# STM32_LED_FROM_MUSIC.net
KiCad netlist of a schematic drawn in Altium Designer
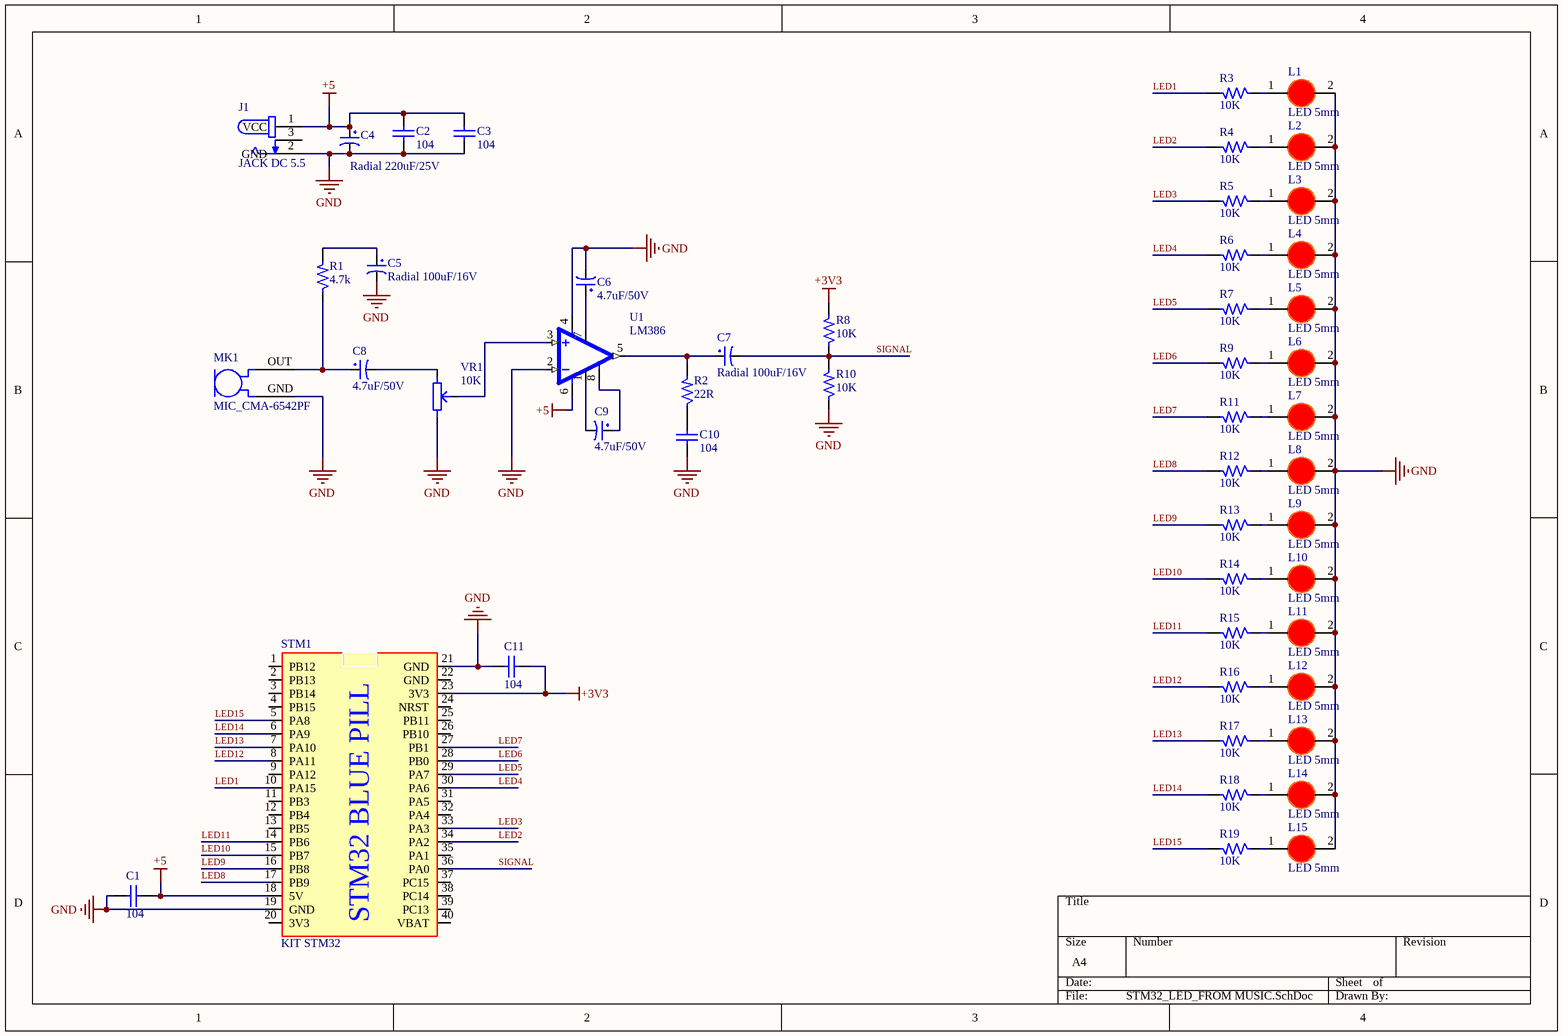
[diagram p0: STM32_LED_FROM MUSIC.SchDoc]

(export (version "E")
  (design (tool "Eeschema 10.0.6"))
  (components
    (comp (ref "C1")
      (value "104")
      (footprint "Cap Ceramic 0805")
      (description "Cap Ceramic SMD")
      (libsource (lib "KS Chuong Real") (part "CAP Ceramic SMD"))
    )
    (comp (ref "C2")
      (value "104")
      (footprint "Cap Ceramic 0805")
      (description "Cap Ceramic SMD")
      (libsource (lib "KS Chuong Real") (part "CAP Ceramic SMD"))
    )
    (comp (ref "C3")
      (value "104")
      (footprint "Cap Ceramic 0805")
      (description "Cap Ceramic SMD")
      (libsource (lib "KS Chuong Real") (part "CAP Ceramic SMD"))
    )
    (comp (ref "C4")
      (value "Radial 220uF/25V")
      (footprint "Radial 6.3x12mm")
      (libsource (lib "KS Chuong Real") (part "Radial 220uF/25V"))
    )
    (comp (ref "C5")
      (value "Radial 100uF/16V")
      (footprint "Radial 5x11mm")
      (libsource (lib "KS Chuong Real") (part "Radial 100uF/16V"))
    )
    (comp (ref "C6")
      (value "4.7uF/50V")
      (footprint "Radial 4.7uF/50V")
      (description "Radial 4.7uF/50V")
      (libsource (lib "") (part "Radial 4.7uF/50V_2"))
    )
    (comp (ref "C7")
      (value "Radial 100uF/16V")
      (footprint "Radial 5x11mm")
      (libsource (lib "") (part "Radial 100uF/16V_1"))
    )
    (comp (ref "C8")
      (value "4.7uF/50V")
      (footprint "Radial 4.7uF/50V")
      (description "Radial 4.7uF/50V")
      (libsource (lib "") (part "Radial 4.7uF/50V_1"))
    )
    (comp (ref "C9")
      (value "4.7uF/50V")
      (footprint "Radial 4.7uF/50V")
      (description "Radial 4.7uF/50V")
      (libsource (lib "KS Chuong Real") (part "Radial 4.7uF/50V"))
    )
    (comp (ref "C10")
      (value "104")
      (footprint "Cap Ceramic 0805")
      (description "Cap Ceramic SMD")
      (libsource (lib "KS Chuong Real") (part "CAP Ceramic SMD"))
    )
    (comp (ref "C11")
      (value "104")
      (footprint "Cap Ceramic 0805")
      (description "Cap Ceramic SMD")
      (libsource (lib "KS Chuong Real") (part "CAP Ceramic SMD"))
    )
    (comp (ref "J1")
      (value "JACK DC 5.5")
      (footprint "JACK DC")
      (description "2,0 x 6,5 mm, 2,5 A, Yatay, A莽谋k Delik, Dc G眉莽 Jak谋 Konnekt枚r眉")
      (fields (field (name "MF") "CUI Devices") (field (name "MP") "PJ-002A"))
      (libsource (lib "KS Chuong Real") (part "JACK DC 5.5"))
    )
    (comp (ref "L1")
      (value "LED 5mm")
      (footprint "LED-5MM-RED")
      (description "Cắm")
      (libsource (lib "KS Chuong Real") (part "LED 5mm Red"))
    )
    (comp (ref "L2")
      (value "LED 5mm")
      (footprint "LED-5MM-RED")
      (description "Cắm")
      (libsource (lib "KS Chuong Real") (part "LED 5mm Red"))
    )
    (comp (ref "L3")
      (value "LED 5mm")
      (footprint "LED-5MM-RED")
      (description "Cắm")
      (libsource (lib "KS Chuong Real") (part "LED 5mm Red"))
    )
    (comp (ref "L4")
      (value "LED 5mm")
      (footprint "LED-5MM-RED")
      (description "Cắm")
      (libsource (lib "KS Chuong Real") (part "LED 5mm Red"))
    )
    (comp (ref "L5")
      (value "LED 5mm")
      (footprint "LED-5MM-RED")
      (description "Cắm")
      (libsource (lib "KS Chuong Real") (part "LED 5mm Red"))
    )
    (comp (ref "L6")
      (value "LED 5mm")
      (footprint "LED-5MM-RED")
      (description "Cắm")
      (libsource (lib "KS Chuong Real") (part "LED 5mm Red"))
    )
    (comp (ref "L7")
      (value "LED 5mm")
      (footprint "LED-5MM-RED")
      (description "Cắm")
      (libsource (lib "KS Chuong Real") (part "LED 5mm Red"))
    )
    (comp (ref "L8")
      (value "LED 5mm")
      (footprint "LED-5MM-RED")
      (description "Cắm")
      (libsource (lib "KS Chuong Real") (part "LED 5mm Red"))
    )
    (comp (ref "L9")
      (value "LED 5mm")
      (footprint "LED-5MM-RED")
      (description "Cắm")
      (libsource (lib "KS Chuong Real") (part "LED 5mm Red"))
    )
    (comp (ref "L10")
      (value "LED 5mm")
      (footprint "LED-5MM-RED")
      (description "Cắm")
      (libsource (lib "KS Chuong Real") (part "LED 5mm Red"))
    )
    (comp (ref "L11")
      (value "LED 5mm")
      (footprint "LED-5MM-RED")
      (description "Cắm")
      (libsource (lib "KS Chuong Real") (part "LED 5mm Red"))
    )
    (comp (ref "L12")
      (value "LED 5mm")
      (footprint "LED-5MM-RED")
      (description "Cắm")
      (libsource (lib "KS Chuong Real") (part "LED 5mm Red"))
    )
    (comp (ref "L13")
      (value "LED 5mm")
      (footprint "LED-5MM-RED")
      (description "Cắm")
      (libsource (lib "KS Chuong Real") (part "LED 5mm Red"))
    )
    (comp (ref "L14")
      (value "LED 5mm")
      (footprint "LED-5MM-RED")
      (description "Cắm")
      (libsource (lib "KS Chuong Real") (part "LED 5mm Red"))
    )
    (comp (ref "L15")
      (value "LED 5mm")
      (footprint "LED-5MM-RED")
      (description "Cắm")
      (libsource (lib "KS Chuong Real") (part "LED 5mm Red"))
    )
    (comp (ref "MK1")
      (value "MIC_CMA-6542PF")
      (footprint "CUI_CMA-6542PF")
      (description "9.7 mm, Omnidirectional, PCB Mount, 4.5 Vdc, Electret Condenser Microphone")
      (fields (field (name "MP") "CMA-6542PF") (field (name "MF") "CUI Devices"))
      (libsource (lib "Chuong Engineer Real") (part "MIC_CMA-6542PF"))
    )
    (comp (ref "R1")
      (value "4.7k")
      (footprint "Res_0805")
      (libsource (lib "KS Chuong Real") (part "Res SMD"))
    )
    (comp (ref "R2") (value "22R") (footprint "Res_0805") (libsource (lib "KS Chuong Real") (part "Res SMD")))
    (comp (ref "R3") (value "10K") (footprint "Res_0805") (libsource (lib "KS Chuong Real") (part "Res SMD")))
    (comp (ref "R4") (value "10K") (footprint "Res_0805") (libsource (lib "KS Chuong Real") (part "Res SMD")))
    (comp (ref "R5") (value "10K") (footprint "Res_0805") (libsource (lib "KS Chuong Real") (part "Res SMD")))
    (comp (ref "R6") (value "10K") (footprint "Res_0805") (libsource (lib "KS Chuong Real") (part "Res SMD")))
    (comp (ref "R7") (value "10K") (footprint "Res_0805") (libsource (lib "KS Chuong Real") (part "Res SMD")))
    (comp (ref "R8") (value "10K") (footprint "Res_0805") (libsource (lib "KS Chuong Real") (part "Res SMD")))
    (comp (ref "R9") (value "10K") (footprint "Res_0805") (libsource (lib "KS Chuong Real") (part "Res SMD")))
    (comp (ref "R10")
      (value "10K")
      (footprint "Res_0805")
      (libsource (lib "KS Chuong Real") (part "Res SMD"))
    )
    (comp (ref "R11")
      (value "10K")
      (footprint "Res_0805")
      (libsource (lib "KS Chuong Real") (part "Res SMD"))
    )
    (comp (ref "R12")
      (value "10K")
      (footprint "Res_0805")
      (libsource (lib "KS Chuong Real") (part "Res SMD"))
    )
    (comp (ref "R13")
      (value "10K")
      (footprint "Res_0805")
      (libsource (lib "KS Chuong Real") (part "Res SMD"))
    )
    (comp (ref "R14")
      (value "10K")
      (footprint "Res_0805")
      (libsource (lib "KS Chuong Real") (part "Res SMD"))
    )
    (comp (ref "R15")
      (value "10K")
      (footprint "Res_0805")
      (libsource (lib "KS Chuong Real") (part "Res SMD"))
    )
    (comp (ref "R16")
      (value "10K")
      (footprint "Res_0805")
      (libsource (lib "KS Chuong Real") (part "Res SMD"))
    )
    (comp (ref "R17")
      (value "10K")
      (footprint "Res_0805")
      (libsource (lib "KS Chuong Real") (part "Res SMD"))
    )
    (comp (ref "R18")
      (value "10K")
      (footprint "Res_0805")
      (libsource (lib "KS Chuong Real") (part "Res SMD"))
    )
    (comp (ref "R19")
      (value "10K")
      (footprint "Res_0805")
      (libsource (lib "KS Chuong Real") (part "Res SMD"))
    )
    (comp (ref "STM1")
      (value "KIT STM32")
      (footprint "STM32 blue pill")
      (description "STM32 BLUE PILL")
      (libsource (lib "KS Chuong Real") (part "STM32 BLUE PILL"))
    )
    (comp (ref "U1")
      (value "LM386")
      (footprint "LM358SMD")
      (description "low voltage audio power amplifier")
      (libsource (lib "Chuong Engineer Real") (part "LM386"))
    )
    (comp (ref "VR1")
      (value "10K")
      (footprint "Bien Tro Tam Giac Dung")
      (description "Cắm")
      (libsource (lib "KS Chuong Real") (part "Potentiometer triangle lie"))
    )
  )
  (nets
    (net (code "1") (name "+3V3") (class "Default")
      (node (ref "C11") (pin "2") (pinfunction "2_2") (pintype "passive"))
      (node (ref "R8") (pin "2") (pinfunction "2_2") (pintype "passive"))
      (node (ref "STM1") (pin "23") (pinfunction "3V3_23") (pintype "passive"))
    )
    (net (code "2") (name "+5") (class "Default")
      (node (ref "C1") (pin "2") (pinfunction "2_2") (pintype "passive"))
      (node (ref "C2") (pin "2") (pinfunction "2_2") (pintype "passive"))
      (node (ref "C3") (pin "2") (pinfunction "2_2") (pintype "passive"))
      (node (ref "C4") (pin "1") (pinfunction "1_1") (pintype "passive"))
      (node (ref "J1") (pin "1") (pinfunction "VCC_1") (pintype "passive"))
      (node (ref "STM1") (pin "18") (pinfunction "5V_18") (pintype "passive"))
      (node (ref "U1") (pin "6") (pinfunction "V+_6") (pintype "power_in"))
    )
    (net (code "3") (name "/LED1") (class "Default")
      (node (ref "R3") (pin "2") (pinfunction "2_2") (pintype "passive"))
      (node (ref "STM1") (pin "10") (pinfunction "PA15_10") (pintype "passive"))
    )
    (net (code "4") (name "/LED2") (class "Default")
      (node (ref "R4") (pin "2") (pinfunction "2_2") (pintype "passive"))
      (node (ref "STM1") (pin "34") (pinfunction "PA2_34") (pintype "passive"))
    )
    (net (code "5") (name "/LED3") (class "Default")
      (node (ref "R5") (pin "2") (pinfunction "2_2") (pintype "passive"))
      (node (ref "STM1") (pin "33") (pinfunction "PA3_33") (pintype "passive"))
    )
    (net (code "6") (name "/LED4") (class "Default")
      (node (ref "R6") (pin "2") (pinfunction "2_2") (pintype "passive"))
      (node (ref "STM1") (pin "30") (pinfunction "PA6_30") (pintype "passive"))
    )
    (net (code "7") (name "/LED5") (class "Default")
      (node (ref "R7") (pin "2") (pinfunction "2_2") (pintype "passive"))
      (node (ref "STM1") (pin "29") (pinfunction "PA7_29") (pintype "passive"))
    )
    (net (code "8") (name "/LED6") (class "Default")
      (node (ref "R9") (pin "2") (pinfunction "2_2") (pintype "passive"))
      (node (ref "STM1") (pin "28") (pinfunction "PB0_28") (pintype "passive"))
    )
    (net (code "9") (name "/LED7") (class "Default")
      (node (ref "R11") (pin "2") (pinfunction "2_2") (pintype "passive"))
      (node (ref "STM1") (pin "27") (pinfunction "PB1_27") (pintype "passive"))
    )
    (net (code "10") (name "/LED8") (class "Default")
      (node (ref "R12") (pin "2") (pinfunction "2_2") (pintype "passive"))
      (node (ref "STM1") (pin "17") (pinfunction "PB9_17") (pintype "passive"))
    )
    (net (code "11") (name "/LED9") (class "Default")
      (node (ref "R13") (pin "2") (pinfunction "2_2") (pintype "passive"))
      (node (ref "STM1") (pin "16") (pinfunction "PB8_16") (pintype "passive"))
    )
    (net (code "12") (name "/LED10") (class "Default")
      (node (ref "R14") (pin "2") (pinfunction "2_2") (pintype "passive"))
      (node (ref "STM1") (pin "15") (pinfunction "PB7_15") (pintype "passive"))
    )
    (net (code "13") (name "/LED11") (class "Default")
      (node (ref "R15") (pin "2") (pinfunction "2_2") (pintype "passive"))
      (node (ref "STM1") (pin "14") (pinfunction "PB6_14") (pintype "passive"))
    )
    (net (code "14") (name "/LED12") (class "Default")
      (node (ref "R16") (pin "2") (pinfunction "2_2") (pintype "passive"))
      (node (ref "STM1") (pin "8") (pinfunction "PA11_8") (pintype "passive"))
    )
    (net (code "15") (name "/LED13") (class "Default")
      (node (ref "R17") (pin "2") (pinfunction "2_2") (pintype "passive"))
      (node (ref "STM1") (pin "7") (pinfunction "PA10_7") (pintype "passive"))
    )
    (net (code "16") (name "/LED14") (class "Default")
      (node (ref "R18") (pin "2") (pinfunction "2_2") (pintype "passive"))
      (node (ref "STM1") (pin "6") (pinfunction "PA9_6") (pintype "passive"))
    )
    (net (code "17") (name "/LED15") (class "Default")
      (node (ref "R19") (pin "2") (pinfunction "2_2") (pintype "passive"))
      (node (ref "STM1") (pin "5") (pinfunction "PA8_5") (pintype "passive"))
    )
    (net (code "18") (name "/SIGNAL") (class "Default")
      (node (ref "C7") (pin "2") (pinfunction "2_2") (pintype "passive"))
      (node (ref "R10") (pin "2") (pinfunction "2_2") (pintype "passive"))
      (node (ref "R8") (pin "1") (pinfunction "1_1") (pintype "passive"))
      (node (ref "STM1") (pin "36") (pinfunction "PA0_36") (pintype "passive"))
    )
    (net (code "19") (name "GND") (class "Default")
      (node (ref "C1") (pin "1") (pinfunction "1_1") (pintype "passive"))
      (node (ref "C10") (pin "1") (pinfunction "1_1") (pintype "passive"))
      (node (ref "C11") (pin "1") (pinfunction "1_1") (pintype "passive"))
      (node (ref "C2") (pin "1") (pinfunction "1_1") (pintype "passive"))
      (node (ref "C3") (pin "1") (pinfunction "1_1") (pintype "passive"))
      (node (ref "C4") (pin "2") (pinfunction "2_2") (pintype "passive"))
      (node (ref "C5") (pin "2") (pinfunction "2_2") (pintype "passive"))
      (node (ref "C6") (pin "2") (pinfunction "2_2") (pintype "passive"))
      (node (ref "J1") (pin "2") (pinfunction "GND_2") (pintype "passive"))
      (node (ref "L1") (pin "2") (pinfunction "K_2") (pintype "passive"))
      (node (ref "L10") (pin "2") (pinfunction "K_2") (pintype "passive"))
      (node (ref "L11") (pin "2") (pinfunction "K_2") (pintype "passive"))
      (node (ref "L12") (pin "2") (pinfunction "K_2") (pintype "passive"))
      (node (ref "L13") (pin "2") (pinfunction "K_2") (pintype "passive"))
      (node (ref "L14") (pin "2") (pinfunction "K_2") (pintype "passive"))
      (node (ref "L15") (pin "2") (pinfunction "K_2") (pintype "passive"))
      (node (ref "L2") (pin "2") (pinfunction "K_2") (pintype "passive"))
      (node (ref "L3") (pin "2") (pinfunction "K_2") (pintype "passive"))
      (node (ref "L4") (pin "2") (pinfunction "K_2") (pintype "passive"))
      (node (ref "L5") (pin "2") (pinfunction "K_2") (pintype "passive"))
      (node (ref "L6") (pin "2") (pinfunction "K_2") (pintype "passive"))
      (node (ref "L7") (pin "2") (pinfunction "K_2") (pintype "passive"))
      (node (ref "L8") (pin "2") (pinfunction "K_2") (pintype "passive"))
      (node (ref "L9") (pin "2") (pinfunction "K_2") (pintype "passive"))
      (node (ref "MK1") (pin "GND") (pinfunction "GND_GND") (pintype "passive"))
      (node (ref "R10") (pin "1") (pinfunction "1_1") (pintype "passive"))
      (node (ref "STM1") (pin "19") (pinfunction "GND_19") (pintype "passive"))
      (node (ref "STM1") (pin "21") (pinfunction "GND_21") (pintype "passive"))
      (node (ref "U1") (pin "2") (pinfunction "-IN_2") (pintype "input"))
      (node (ref "U1") (pin "4") (pinfunction "V-_4") (pintype "power_in"))
      (node (ref "VR1") (pin "3") (pinfunction "3_3") (pintype "passive"))
    )
    (net (code "20") (name "Net-(C5-Pad1)") (class "Default")
      (node (ref "C5") (pin "1") (pinfunction "1_1") (pintype "passive"))
      (node (ref "R1") (pin "2") (pinfunction "2_2") (pintype "passive"))
    )
    (net (code "21") (name "Net-(C8-Pad1)") (class "Default")
      (node (ref "C8") (pin "1") (pinfunction "1_1") (pintype "passive"))
      (node (ref "MK1") (pin "OUT") (pinfunction "OUT_OUT") (pintype "passive"))
      (node (ref "R1") (pin "1") (pinfunction "1_1") (pintype "passive"))
    )
    (net (code "22") (name "Net-(C8-Pad2)") (class "Default")
      (node (ref "C8") (pin "2") (pinfunction "2_2") (pintype "passive"))
      (node (ref "VR1") (pin "1") (pinfunction "1_1") (pintype "passive"))
    )
    (net (code "23") (name "Net-(C10-Pad2)") (class "Default")
      (node (ref "C10") (pin "2") (pinfunction "2_2") (pintype "passive"))
      (node (ref "R2") (pin "1") (pinfunction "1_1") (pintype "passive"))
    )
    (net (code "24") (name "Net-(L1-A)") (class "Default")
      (node (ref "L1") (pin "1") (pinfunction "A_1") (pintype "passive"))
      (node (ref "R3") (pin "1") (pinfunction "1_1") (pintype "passive"))
    )
    (net (code "25") (name "Net-(L2-A)") (class "Default")
      (node (ref "L2") (pin "1") (pinfunction "A_1") (pintype "passive"))
      (node (ref "R4") (pin "1") (pinfunction "1_1") (pintype "passive"))
    )
    (net (code "26") (name "Net-(L3-A)") (class "Default")
      (node (ref "L3") (pin "1") (pinfunction "A_1") (pintype "passive"))
      (node (ref "R5") (pin "1") (pinfunction "1_1") (pintype "passive"))
    )
    (net (code "27") (name "Net-(L4-A)") (class "Default")
      (node (ref "L4") (pin "1") (pinfunction "A_1") (pintype "passive"))
      (node (ref "R6") (pin "1") (pinfunction "1_1") (pintype "passive"))
    )
    (net (code "28") (name "Net-(L5-A)") (class "Default")
      (node (ref "L5") (pin "1") (pinfunction "A_1") (pintype "passive"))
      (node (ref "R7") (pin "1") (pinfunction "1_1") (pintype "passive"))
    )
    (net (code "29") (name "Net-(L6-A)") (class "Default")
      (node (ref "L6") (pin "1") (pinfunction "A_1") (pintype "passive"))
      (node (ref "R9") (pin "1") (pinfunction "1_1") (pintype "passive"))
    )
    (net (code "30") (name "Net-(L7-A)") (class "Default")
      (node (ref "L7") (pin "1") (pinfunction "A_1") (pintype "passive"))
      (node (ref "R11") (pin "1") (pinfunction "1_1") (pintype "passive"))
    )
    (net (code "31") (name "Net-(L8-A)") (class "Default")
      (node (ref "L8") (pin "1") (pinfunction "A_1") (pintype "passive"))
      (node (ref "R12") (pin "1") (pinfunction "1_1") (pintype "passive"))
    )
    (net (code "32") (name "Net-(L9-A)") (class "Default")
      (node (ref "L9") (pin "1") (pinfunction "A_1") (pintype "passive"))
      (node (ref "R13") (pin "1") (pinfunction "1_1") (pintype "passive"))
    )
    (net (code "33") (name "Net-(L10-A)") (class "Default")
      (node (ref "L10") (pin "1") (pinfunction "A_1") (pintype "passive"))
      (node (ref "R14") (pin "1") (pinfunction "1_1") (pintype "passive"))
    )
    (net (code "34") (name "Net-(L11-A)") (class "Default")
      (node (ref "L11") (pin "1") (pinfunction "A_1") (pintype "passive"))
      (node (ref "R15") (pin "1") (pinfunction "1_1") (pintype "passive"))
    )
    (net (code "35") (name "Net-(L12-A)") (class "Default")
      (node (ref "L12") (pin "1") (pinfunction "A_1") (pintype "passive"))
      (node (ref "R16") (pin "1") (pinfunction "1_1") (pintype "passive"))
    )
    (net (code "36") (name "Net-(L13-A)") (class "Default")
      (node (ref "L13") (pin "1") (pinfunction "A_1") (pintype "passive"))
      (node (ref "R17") (pin "1") (pinfunction "1_1") (pintype "passive"))
    )
    (net (code "37") (name "Net-(L14-A)") (class "Default")
      (node (ref "L14") (pin "1") (pinfunction "A_1") (pintype "passive"))
      (node (ref "R18") (pin "1") (pinfunction "1_1") (pintype "passive"))
    )
    (net (code "38") (name "Net-(L15-A)") (class "Default")
      (node (ref "L15") (pin "1") (pinfunction "A_1") (pintype "passive"))
      (node (ref "R19") (pin "1") (pinfunction "1_1") (pintype "passive"))
    )
    (net (code "39") (name "Net-(U1-+IN)") (class "Default")
      (node (ref "U1") (pin "3") (pinfunction "+IN_3") (pintype "input"))
      (node (ref "VR1") (pin "2") (pinfunction "2_2") (pintype "passive"))
    )
    (net (code "40") (name "Net-(U1-BP)") (class "Default")
      (node (ref "C6") (pin "1") (pinfunction "1_1") (pintype "passive"))
      (node (ref "U1") (pin "7") (pinfunction "BP_7") (pintype "bidirectional"))
    )
    (net (code "41") (name "Net-(U1-GAIN@1)") (class "Default")
      (node (ref "C9") (pin "2") (pinfunction "2_2") (pintype "passive"))
      (node (ref "U1") (pin "1") (pinfunction "GAIN@1_1") (pintype "bidirectional"))
    )
    (net (code "42") (name "Net-(U1-GAIN@8)") (class "Default")
      (node (ref "C9") (pin "1") (pinfunction "1_1") (pintype "passive"))
      (node (ref "U1") (pin "8") (pinfunction "GAIN@8_8") (pintype "bidirectional"))
    )
    (net (code "43") (name "Net-(U1-OUT)") (class "Default")
      (node (ref "C7") (pin "1") (pinfunction "1_1") (pintype "passive"))
      (node (ref "R2") (pin "2") (pinfunction "2_2") (pintype "passive"))
      (node (ref "U1") (pin "5") (pinfunction "OUT_5") (pintype "output"))
    )
    (net (code "44") (name "unconnected-(J1-Pad3)") (class "Default")
      (node (ref "J1") (pin "3") (pinfunction "3_3") (pintype "passive"))
    )
    (net (code "45") (name "unconnected-(STM1-3V3-Pad20)") (class "Default")
      (node (ref "STM1") (pin "20") (pinfunction "3V3_20") (pintype "passive"))
    )
    (net (code "46") (name "unconnected-(STM1-GND-Pad22)") (class "Default")
      (node (ref "STM1") (pin "22") (pinfunction "GND_22") (pintype "passive"))
    )
    (net (code "47") (name "unconnected-(STM1-NRST-Pad24)") (class "Default")
      (node (ref "STM1") (pin "24") (pinfunction "NRST_24") (pintype "passive"))
    )
    (net (code "48") (name "unconnected-(STM1-PA1-Pad35)") (class "Default")
      (node (ref "STM1") (pin "35") (pinfunction "PA1_35") (pintype "passive"))
    )
    (net (code "49") (name "unconnected-(STM1-PA4-Pad32)") (class "Default")
      (node (ref "STM1") (pin "32") (pinfunction "PA4_32") (pintype "passive"))
    )
    (net (code "50") (name "unconnected-(STM1-PA5-Pad31)") (class "Default")
      (node (ref "STM1") (pin "31") (pinfunction "PA5_31") (pintype "passive"))
    )
    (net (code "51") (name "unconnected-(STM1-PA12-Pad9)") (class "Default")
      (node (ref "STM1") (pin "9") (pinfunction "PA12_9") (pintype "passive"))
    )
    (net (code "52") (name "unconnected-(STM1-PB3-Pad11)") (class "Default")
      (node (ref "STM1") (pin "11") (pinfunction "PB3_11") (pintype "passive"))
    )
    (net (code "53") (name "unconnected-(STM1-PB4-Pad12)") (class "Default")
      (node (ref "STM1") (pin "12") (pinfunction "PB4_12") (pintype "passive"))
    )
    (net (code "54") (name "unconnected-(STM1-PB5-Pad13)") (class "Default")
      (node (ref "STM1") (pin "13") (pinfunction "PB5_13") (pintype "passive"))
    )
    (net (code "55") (name "unconnected-(STM1-PB10-Pad26)") (class "Default")
      (node (ref "STM1") (pin "26") (pinfunction "PB10_26") (pintype "passive"))
    )
    (net (code "56") (name "unconnected-(STM1-PB11-Pad25)") (class "Default")
      (node (ref "STM1") (pin "25") (pinfunction "PB11_25") (pintype "passive"))
    )
    (net (code "57") (name "unconnected-(STM1-PB12-Pad1)") (class "Default")
      (node (ref "STM1") (pin "1") (pinfunction "PB12_1") (pintype "passive"))
    )
    (net (code "58") (name "unconnected-(STM1-PB13-Pad2)") (class "Default")
      (node (ref "STM1") (pin "2") (pinfunction "PB13_2") (pintype "passive"))
    )
    (net (code "59") (name "unconnected-(STM1-PB14-Pad3)") (class "Default")
      (node (ref "STM1") (pin "3") (pinfunction "PB14_3") (pintype "passive"))
    )
    (net (code "60") (name "unconnected-(STM1-PB15-Pad4)") (class "Default")
      (node (ref "STM1") (pin "4") (pinfunction "PB15_4") (pintype "passive"))
    )
    (net (code "61") (name "unconnected-(STM1-PC13-Pad39)") (class "Default")
      (node (ref "STM1") (pin "39") (pinfunction "PC13_39") (pintype "passive"))
    )
    (net (code "62") (name "unconnected-(STM1-PC14-Pad38)") (class "Default")
      (node (ref "STM1") (pin "38") (pinfunction "PC14_38") (pintype "passive"))
    )
    (net (code "63") (name "unconnected-(STM1-PC15-Pad37)") (class "Default")
      (node (ref "STM1") (pin "37") (pinfunction "PC15_37") (pintype "passive"))
    )
    (net (code "64") (name "unconnected-(STM1-VBAT-Pad40)") (class "Default")
      (node (ref "STM1") (pin "40") (pinfunction "VBAT_40") (pintype "passive"))
    )
  )
)
